# Sheet1.net
KiCad netlist of a schematic drawn in Altium Designer
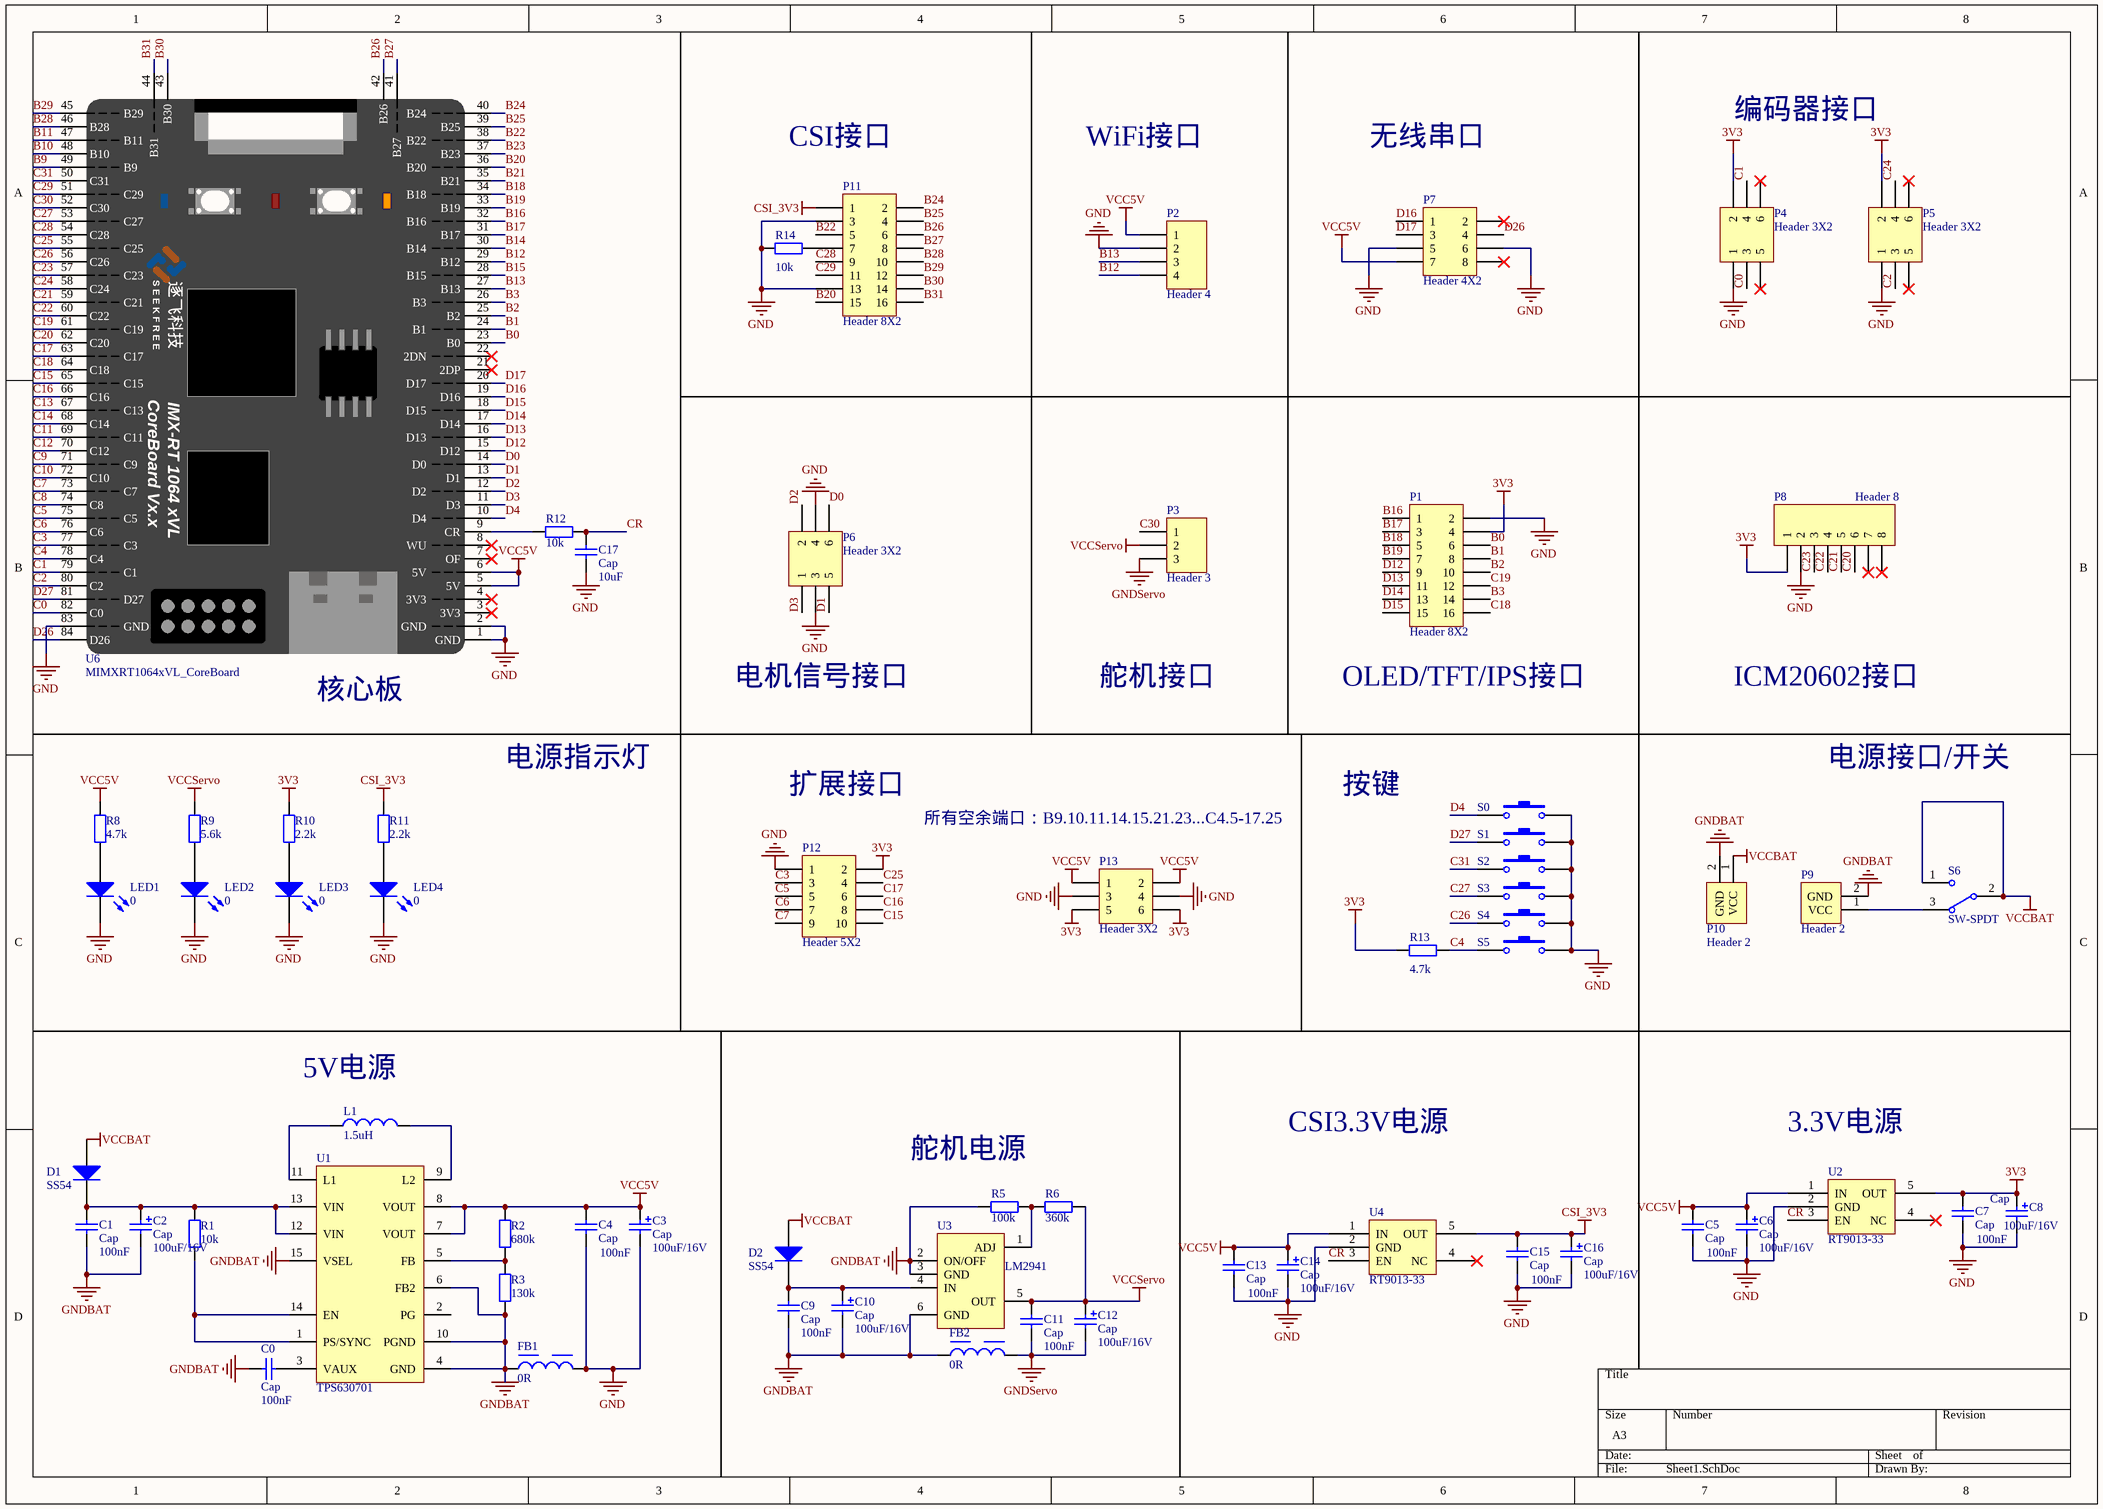
[diagram p0: Sheet1.SchDoc]

(export (version "E")
  (design (tool "Eeschema 10.0.6"))
  (components
    (comp (ref "C0")
      (value "Cap")
      (footprint "0603C")
      (description "Capacitor")
      (fields (field (name "ALTIUM_VALUE") "100nF") (field (name "PUBLISHER") "Altium Limited"))
      (libsource (lib "Schlib1") (part "Cap"))
    )
    (comp (ref "C1")
      (value "Cap")
      (footprint "0603C")
      (description "Capacitor")
      (fields (field (name "ALTIUM_VALUE") "100nF") (field (name "PUBLISHER") "Altium Limited"))
      (libsource (lib "Schlib1") (part "Cap"))
    )
    (comp (ref "C2")
      (value "Cap")
      (footprint "电解电容")
      (description "Capacitor")
      (fields (field (name "ALTIUM_VALUE") "100uF/16V") (field (name "PUBLISHER") "Altium Limited"))
      (libsource (lib "Schlib1") (part "Cap2"))
    )
    (comp (ref "C3")
      (value "Cap")
      (footprint "电解电容")
      (description "Capacitor")
      (fields (field (name "ALTIUM_VALUE") "100uF/16V") (field (name "PUBLISHER") "Altium Limited"))
      (libsource (lib "Schlib1") (part "Cap2"))
    )
    (comp (ref "C4")
      (value "Cap")
      (footprint "0603C")
      (description "Capacitor")
      (fields (field (name "ALTIUM_VALUE") "100nF") (field (name "PUBLISHER") "Altium Limited"))
      (libsource (lib "Schlib1") (part "Cap"))
    )
    (comp (ref "C5")
      (value "Cap")
      (footprint "0603C")
      (description "Capacitor")
      (fields (field (name "ALTIUM_VALUE") "100nF") (field (name "PUBLISHER") "Altium Limited"))
      (libsource (lib "Schlib1") (part "Cap"))
    )
    (comp (ref "C6")
      (value "Cap")
      (footprint "电解电容")
      (description "Capacitor")
      (fields (field (name "ALTIUM_VALUE") "100uF/16V") (field (name "PUBLISHER") "Altium Limited"))
      (libsource (lib "Schlib1") (part "Cap2"))
    )
    (comp (ref "C7")
      (value "Cap")
      (footprint "0603C")
      (description "Capacitor")
      (fields (field (name "ALTIUM_VALUE") "100nF") (field (name "PUBLISHER") "Altium Limited"))
      (libsource (lib "Schlib1") (part "Cap"))
    )
    (comp (ref "C8")
      (value "Cap")
      (footprint "电解电容")
      (description "Capacitor")
      (fields (field (name "ALTIUM_VALUE") "100uF/16V") (field (name "PUBLISHER") "Altium Limited"))
      (libsource (lib "Schlib1") (part "Cap2"))
    )
    (comp (ref "C9")
      (value "Cap")
      (footprint "0603C")
      (description "Capacitor")
      (fields (field (name "ALTIUM_VALUE") "100nF") (field (name "PUBLISHER") "Altium Limited"))
      (libsource (lib "Schlib1") (part "Cap"))
    )
    (comp (ref "C10")
      (value "Cap")
      (footprint "电解电容")
      (description "Capacitor")
      (fields (field (name "ALTIUM_VALUE") "100uF/16V") (field (name "PUBLISHER") "Altium Limited"))
      (libsource (lib "Schlib1") (part "Cap2"))
    )
    (comp (ref "C11")
      (value "Cap")
      (footprint "0603C")
      (description "Capacitor")
      (fields (field (name "ALTIUM_VALUE") "100nF") (field (name "PUBLISHER") "Altium Limited"))
      (libsource (lib "Schlib1") (part "Cap"))
    )
    (comp (ref "C12")
      (value "Cap")
      (footprint "电解电容")
      (description "Capacitor")
      (fields (field (name "ALTIUM_VALUE") "100uF/16V") (field (name "PUBLISHER") "Altium Limited"))
      (libsource (lib "Schlib1") (part "Cap2"))
    )
    (comp (ref "C13")
      (value "Cap")
      (footprint "0603C")
      (description "Capacitor")
      (fields (field (name "ALTIUM_VALUE") "100nF") (field (name "PUBLISHER") "Altium Limited"))
      (libsource (lib "Schlib1") (part "Cap"))
    )
    (comp (ref "C14")
      (value "Cap")
      (footprint "电解电容")
      (description "Capacitor")
      (fields (field (name "ALTIUM_VALUE") "100uF/16V") (field (name "PUBLISHER") "Altium Limited"))
      (libsource (lib "Schlib1") (part "Cap2"))
    )
    (comp (ref "C15")
      (value "Cap")
      (footprint "0603C")
      (description "Capacitor")
      (fields (field (name "ALTIUM_VALUE") "100nF") (field (name "PUBLISHER") "Altium Limited"))
      (libsource (lib "Schlib1") (part "Cap"))
    )
    (comp (ref "C16")
      (value "Cap")
      (footprint "电解电容")
      (description "Capacitor")
      (fields (field (name "ALTIUM_VALUE") "100uF/16V") (field (name "PUBLISHER") "Altium Limited"))
      (libsource (lib "Schlib1") (part "Cap2"))
    )
    (comp (ref "C17")
      (value "Cap")
      (footprint "0603C")
      (description "Capacitor")
      (fields (field (name "ALTIUM_VALUE") "10uF") (field (name "PUBLISHER") "Altium Limited"))
      (libsource (lib "Schlib1") (part "Cap"))
    )
    (comp (ref "D1")
      (value "SS54")
      (footprint "ss54")
      (description "Default Diode")
      (fields (field (name "PUBLISHER") "Altium Limited"))
      (libsource (lib "Schlib1") (part "Diode_1"))
    )
    (comp (ref "D2")
      (value "SS54")
      (footprint "ss54")
      (description "Default Diode")
      (fields (field (name "PUBLISHER") "Altium Limited"))
      (libsource (lib "Schlib1") (part "Diode_1"))
    )
    (comp (ref "FB1")
      (value "0R")
      (footprint "0805")
      (description "Inductor")
      (fields (field (name "PUBLISHER") "Altium Limited"))
      (libsource (lib "Schlib1") (part "FB"))
    )
    (comp (ref "FB2")
      (value "0R")
      (footprint "0805")
      (description "Inductor")
      (fields (field (name "PUBLISHER") "Altium Limited"))
      (libsource (lib "Schlib1") (part "FB"))
    )
    (comp (ref "L1")
      (value "1.5uH")
      (footprint "1R5")
      (description "Inductor")
      (fields (field (name "PUBLISHER") "Altium Limited"))
      (libsource (lib "Schlib1") (part "Inductor_2"))
    )
    (comp (ref "LED1")
      (value "0")
      (footprint "0603C")
      (description "Typical RED, GREEN, YELLOW, AMBER GaAs LED")
      (fields (field (name "PUBLISHER") "Altium Limited"))
      (libsource (lib "Schlib1") (part "LED2"))
    )
    (comp (ref "LED2")
      (value "0")
      (footprint "0603C")
      (description "Typical RED, GREEN, YELLOW, AMBER GaAs LED")
      (fields (field (name "PUBLISHER") "Altium Limited"))
      (libsource (lib "Schlib1") (part "LED2"))
    )
    (comp (ref "LED3")
      (value "0")
      (footprint "0603C")
      (description "Typical RED, GREEN, YELLOW, AMBER GaAs LED")
      (fields (field (name "PUBLISHER") "Altium Limited"))
      (libsource (lib "Schlib1") (part "LED2"))
    )
    (comp (ref "LED4")
      (value "0")
      (footprint "0603C")
      (description "Typical RED, GREEN, YELLOW, AMBER GaAs LED")
      (fields (field (name "PUBLISHER") "Altium Limited"))
      (libsource (lib "Schlib1") (part "LED2"))
    )
    (comp (ref "P1")
      (value "Header 8X2")
      (footprint "HDR2X8")
      (description "Header, 8-Pin, Dual row")
      (fields (field (name "PUBLISHER") "Altium Limited"))
      (libsource (lib "Miscellaneous Connectors") (part "Header 8X2"))
    )
    (comp (ref "P2")
      (value "Header 4")
      (footprint "HDR1X4")
      (description "Header, 4-Pin")
      (fields (field (name "PUBLISHER") "Altium Limited"))
      (libsource (lib "Miscellaneous Connectors") (part "Header 4"))
    )
    (comp (ref "P3")
      (value "Header 3")
      (footprint "HDR1X3")
      (description "Header, 3-Pin")
      (fields (field (name "PUBLISHER") "Altium Limited"))
      (libsource (lib "Miscellaneous Connectors") (part "Header 3"))
    )
    (comp (ref "P4")
      (value "Header 3X2")
      (footprint "HDR2X3")
      (description "Header, 3-Pin, Dual row")
      (fields (field (name "PUBLISHER") "Altium Limited"))
      (libsource (lib "Miscellaneous Connectors") (part "Header 3X2"))
    )
    (comp (ref "P5")
      (value "Header 3X2")
      (footprint "HDR2X3")
      (description "Header, 3-Pin, Dual row")
      (fields (field (name "PUBLISHER") "Altium Limited"))
      (libsource (lib "Miscellaneous Connectors") (part "Header 3X2"))
    )
    (comp (ref "P6")
      (value "Header 3X2")
      (footprint "HDR2X3")
      (description "Header, 3-Pin, Dual row")
      (fields (field (name "PUBLISHER") "Altium Limited"))
      (libsource (lib "Miscellaneous Connectors") (part "Header 3X2"))
    )
    (comp (ref "P7")
      (value "Header 4X2")
      (footprint "HDR2X4")
      (description "Header, 4-Pin, Dual row")
      (fields (field (name "PUBLISHER") "Altium Limited"))
      (libsource (lib "Miscellaneous Connectors") (part "Header 4X2"))
    )
    (comp (ref "P8")
      (value "Header 8")
      (footprint "HDR1X8")
      (description "Header, 8-Pin")
      (fields (field (name "PUBLISHER") "Altium Limited"))
      (libsource (lib "Miscellaneous Connectors") (part "Header 8"))
    )
    (comp (ref "P9")
      (value "Header 2")
      (footprint "VCCBAT")
      (description "Header, 2-Pin")
      (fields (field (name "PUBLISHER") "Altium Limited"))
      (libsource (lib "Schlib1") (part "Header 2_1"))
    )
    (comp (ref "P10")
      (value "Header 2")
      (footprint "VCCBAT")
      (description "Header, 2-Pin")
      (fields (field (name "PUBLISHER") "Altium Limited"))
      (libsource (lib "Schlib1") (part "Header 2_2"))
    )
    (comp (ref "P11")
      (value "Header 8X2")
      (footprint "HDR2X8")
      (description "Header, 8-Pin, Dual row")
      (fields (field (name "PUBLISHER") "Altium Limited"))
      (libsource (lib "Miscellaneous Connectors") (part "Header 8X2"))
    )
    (comp (ref "P12")
      (value "Header 5X2")
      (footprint "HDR2X5")
      (description "Header, 5-Pin, Dual row")
      (fields (field (name "PUBLISHER") "Altium Limited"))
      (libsource (lib "Miscellaneous Connectors") (part "Header 5X2"))
    )
    (comp (ref "P13")
      (value "Header 3X2")
      (footprint "HDR2X3")
      (description "Header, 3-Pin, Dual row")
      (fields (field (name "PUBLISHER") "Altium Limited"))
      (libsource (lib "") (part "Header 3X2_1"))
    )
    (comp (ref "R1")
      (value "10k")
      (footprint "0603R")
      (description "Resistor")
      (fields (field (name "Comment") "Res2") (field (name "PUBLISHER") "Altium Limited"))
      (libsource (lib "Schlib1") (part "Res2"))
    )
    (comp (ref "R2")
      (value "680k")
      (footprint "0603R")
      (description "Resistor")
      (fields (field (name "Comment") "Res2") (field (name "PUBLISHER") "Altium Limited"))
      (libsource (lib "Schlib1") (part "Res2"))
    )
    (comp (ref "R3")
      (value "130k")
      (footprint "0603R")
      (description "Resistor 改成了120k")
      (fields (field (name "Comment") "Res2") (field (name "PUBLISHER") "Altium Limited"))
      (libsource (lib "Schlib1") (part "Res2"))
    )
    (comp (ref "R5")
      (value "100k")
      (footprint "0603R")
      (description "Resistor")
      (fields (field (name "Comment") "Res2") (field (name "PUBLISHER") "Altium Limited"))
      (libsource (lib "") (part "Res2_1"))
    )
    (comp (ref "R6")
      (value "360k")
      (footprint "0603R")
      (description "Resistor 改成了330k")
      (fields (field (name "Comment") "Res2") (field (name "PUBLISHER") "Altium Limited"))
      (libsource (lib "") (part "Res2_1"))
    )
    (comp (ref "R8")
      (value "4.7k")
      (footprint "0603R")
      (description "Resistor")
      (fields (field (name "Comment") "Res2") (field (name "PUBLISHER") "Altium Limited"))
      (libsource (lib "Schlib1") (part "Res2"))
    )
    (comp (ref "R9")
      (value "5.6k")
      (footprint "0603R")
      (description "Resistor改成了5.1k")
      (fields (field (name "Comment") "Res2") (field (name "PUBLISHER") "Altium Limited"))
      (libsource (lib "Schlib1") (part "Res2"))
    )
    (comp (ref "R10")
      (value "2.2k")
      (footprint "0603R")
      (description "Resistor")
      (fields (field (name "Comment") "Res2") (field (name "PUBLISHER") "Altium Limited"))
      (libsource (lib "Schlib1") (part "Res2"))
    )
    (comp (ref "R11")
      (value "2.2k")
      (footprint "0603R")
      (description "Resistor")
      (fields (field (name "Comment") "Res2") (field (name "PUBLISHER") "Altium Limited"))
      (libsource (lib "Schlib1") (part "Res2"))
    )
    (comp (ref "R12")
      (value "10k")
      (footprint "0603R")
      (description "Resistor")
      (fields (field (name "Comment") "Res2") (field (name "PUBLISHER") "Altium Limited"))
      (libsource (lib "") (part "Res2_1"))
    )
    (comp (ref "R13")
      (value "4.7k")
      (footprint "0603R")
      (description "Resistor")
      (fields (field (name "Comment") "Res2") (field (name "PUBLISHER") "Altium Limited"))
      (libsource (lib "") (part "Res2_1"))
    )
    (comp (ref "R14")
      (value "10k")
      (footprint "0603R")
      (description "Resistor")
      (fields (field (name "Comment") "Res2") (field (name "PUBLISHER") "Altium Limited"))
      (libsource (lib "") (part "Res2_1"))
    )
    (comp (ref "S0")
      (value "~")
      (footprint "SPST-2")
      (description "Switch")
      (fields (field (name "PUBLISHER") "Altium Limited"))
      (libsource (lib "Miscellaneous Devices") (part "SW-PB"))
    )
    (comp (ref "S1")
      (value "~")
      (footprint "SPST-2")
      (description "Switch")
      (fields (field (name "PUBLISHER") "Altium Limited"))
      (libsource (lib "Miscellaneous Devices") (part "SW-PB"))
    )
    (comp (ref "S2")
      (value "~")
      (footprint "SPST-2")
      (description "Switch")
      (fields (field (name "PUBLISHER") "Altium Limited"))
      (libsource (lib "Miscellaneous Devices") (part "SW-PB"))
    )
    (comp (ref "S3")
      (value "~")
      (footprint "SPST-2")
      (description "Switch")
      (fields (field (name "PUBLISHER") "Altium Limited"))
      (libsource (lib "Miscellaneous Devices") (part "SW-PB"))
    )
    (comp (ref "S4")
      (value "~")
      (footprint "SPST-2")
      (description "Switch")
      (fields (field (name "PUBLISHER") "Altium Limited"))
      (libsource (lib "Miscellaneous Devices") (part "SW-PB"))
    )
    (comp (ref "S5")
      (value "~")
      (footprint "SPST-2")
      (description "Switch")
      (fields (field (name "PUBLISHER") "Altium Limited"))
      (libsource (lib "Miscellaneous Devices") (part "SW-PB"))
    )
    (comp (ref "S6")
      (value "SW-SPDT")
      (footprint "SW")
      (description "SPDT Subminiature Toggle Switch, Right Angle Mounting, Vertical Actuation")
      (fields (field (name "PUBLISHER") "Altium Limited"))
      (libsource (lib "Miscellaneous Devices") (part "SW-SPDT"))
    )
    (comp (ref "U1") (value "TPS630701") (footprint "63070") (libsource (lib "Schlib1") (part "TPS630701")))
    (comp (ref "U2")
      (value "RT9013-33")
      (footprint "SOT23-5_L")
      (libsource (lib "Schlib1") (part "RT9013-33"))
    )
    (comp (ref "U3")
      (value "LM2941")
      (footprint "TO-263-5L")
      (description "Header, 4-Pin")
      (fields (field (name "PUBLISHER") "Altium Limited"))
      (libsource (lib "Schlib1") (part "LM2941"))
    )
    (comp (ref "U4")
      (value "RT9013-33")
      (footprint "SOT23-5_L")
      (libsource (lib "Schlib1") (part "RT9013-33"))
    )
    (comp (ref "U6")
      (value "MIMXRT1064xVL_CoreBoard")
      (footprint "MIMXRT1064xVL_CoreBoard")
      (description "逐飞科技i.MX RT1064核心板整体原理，可直接使用")
      (libsource (lib "RT1064 V1.2核心板原理库") (part "MIMXRT1064xVL_CoreBoard"))
    )
  )
  (nets
    (net (code "1") (name "/B0") (class "Default")
      (node (ref "P1") (pin "6") (pinfunction "6_6") (pintype "passive"))
      (node (ref "U6") (pin "23") (pinfunction "B0_23") (pintype "passive"))
    )
    (net (code "2") (name "/B1") (class "Default")
      (node (ref "P1") (pin "8") (pinfunction "8_8") (pintype "passive"))
      (node (ref "U6") (pin "24") (pinfunction "B1_24") (pintype "passive"))
    )
    (net (code "3") (name "/B2") (class "Default")
      (node (ref "P1") (pin "10") (pinfunction "10_10") (pintype "passive"))
      (node (ref "U6") (pin "25") (pinfunction "B2_25") (pintype "passive"))
    )
    (net (code "4") (name "/B3") (class "Default")
      (node (ref "P1") (pin "14") (pinfunction "14_14") (pintype "passive"))
      (node (ref "U6") (pin "26") (pinfunction "B3_26") (pintype "passive"))
    )
    (net (code "5") (name "/B9") (class "Default")
      (node (ref "U6") (pin "49") (pinfunction "B9_49") (pintype "passive"))
    )
    (net (code "6") (name "/B10") (class "Default")
      (node (ref "U6") (pin "48") (pinfunction "B10_48") (pintype "passive"))
    )
    (net (code "7") (name "/B11") (class "Default")
      (node (ref "U6") (pin "47") (pinfunction "B11_47") (pintype "passive"))
    )
    (net (code "8") (name "/B12") (class "Default")
      (node (ref "P2") (pin "4") (pinfunction "4_4") (pintype "passive"))
      (node (ref "U6") (pin "29") (pinfunction "B12_29") (pintype "passive"))
    )
    (net (code "9") (name "/B13") (class "Default")
      (node (ref "P2") (pin "3") (pinfunction "3_3") (pintype "passive"))
      (node (ref "U6") (pin "27") (pinfunction "B13_27") (pintype "passive"))
    )
    (net (code "10") (name "/B14") (class "Default")
      (node (ref "U6") (pin "30") (pinfunction "B14_30") (pintype "passive"))
    )
    (net (code "11") (name "/B15") (class "Default")
      (node (ref "U6") (pin "28") (pinfunction "B15_28") (pintype "passive"))
    )
    (net (code "12") (name "/B16") (class "Default")
      (node (ref "P1") (pin "1") (pinfunction "1_1") (pintype "passive"))
      (node (ref "U6") (pin "32") (pinfunction "B16_32") (pintype "passive"))
    )
    (net (code "13") (name "/B17") (class "Default")
      (node (ref "P1") (pin "3") (pinfunction "3_3") (pintype "passive"))
      (node (ref "U6") (pin "31") (pinfunction "B17_31") (pintype "passive"))
    )
    (net (code "14") (name "/B18") (class "Default")
      (node (ref "P1") (pin "5") (pinfunction "5_5") (pintype "passive"))
      (node (ref "U6") (pin "34") (pinfunction "B18_34") (pintype "passive"))
    )
    (net (code "15") (name "/B19") (class "Default")
      (node (ref "P1") (pin "7") (pinfunction "7_7") (pintype "passive"))
      (node (ref "U6") (pin "33") (pinfunction "B19_33") (pintype "passive"))
    )
    (net (code "16") (name "/B20") (class "Default")
      (node (ref "P11") (pin "15") (pinfunction "15_15") (pintype "passive"))
      (node (ref "U6") (pin "36") (pinfunction "B20_36") (pintype "passive"))
    )
    (net (code "17") (name "/B21") (class "Default")
      (node (ref "U6") (pin "35") (pinfunction "B21_35") (pintype "passive"))
    )
    (net (code "18") (name "/B22") (class "Default")
      (node (ref "P11") (pin "5") (pinfunction "5_5") (pintype "passive"))
      (node (ref "U6") (pin "38") (pinfunction "B22_38") (pintype "passive"))
    )
    (net (code "19") (name "/B23") (class "Default")
      (node (ref "U6") (pin "37") (pinfunction "B23_37") (pintype "passive"))
    )
    (net (code "20") (name "/B24") (class "Default")
      (node (ref "P11") (pin "2") (pinfunction "2_2") (pintype "passive"))
      (node (ref "U6") (pin "40") (pinfunction "B24_40") (pintype "passive"))
    )
    (net (code "21") (name "/B25") (class "Default")
      (node (ref "P11") (pin "4") (pinfunction "4_4") (pintype "passive"))
      (node (ref "U6") (pin "39") (pinfunction "B25_39") (pintype "passive"))
    )
    (net (code "22") (name "/B26") (class "Default")
      (node (ref "P11") (pin "6") (pinfunction "6_6") (pintype "passive"))
      (node (ref "U6") (pin "42") (pinfunction "B26_42") (pintype "passive"))
    )
    (net (code "23") (name "/B27") (class "Default")
      (node (ref "P11") (pin "8") (pinfunction "8_8") (pintype "passive"))
      (node (ref "U6") (pin "41") (pinfunction "B27_41") (pintype "passive"))
    )
    (net (code "24") (name "/B28") (class "Default")
      (node (ref "P11") (pin "10") (pinfunction "10_10") (pintype "passive"))
      (node (ref "U6") (pin "46") (pinfunction "B28_46") (pintype "passive"))
    )
    (net (code "25") (name "/B29") (class "Default")
      (node (ref "P11") (pin "12") (pinfunction "12_12") (pintype "passive"))
      (node (ref "U6") (pin "45") (pinfunction "B29_45") (pintype "passive"))
    )
    (net (code "26") (name "/B30") (class "Default")
      (node (ref "P11") (pin "14") (pinfunction "14_14") (pintype "passive"))
      (node (ref "U6") (pin "43") (pinfunction "B30_43") (pintype "passive"))
    )
    (net (code "27") (name "/B31") (class "Default")
      (node (ref "P11") (pin "16") (pinfunction "16_16") (pintype "passive"))
      (node (ref "U6") (pin "44") (pinfunction "B31_44") (pintype "passive"))
    )
    (net (code "28") (name "/C0") (class "Default")
      (node (ref "P4") (pin "3") (pinfunction "3_3") (pintype "passive"))
      (node (ref "U6") (pin "82") (pinfunction "C0_82") (pintype "passive"))
    )
    (net (code "29") (name "/C1") (class "Default")
      (node (ref "P4") (pin "4") (pinfunction "4_4") (pintype "passive"))
      (node (ref "U6") (pin "79") (pinfunction "C1_79") (pintype "passive"))
    )
    (net (code "30") (name "/C2") (class "Default")
      (node (ref "P5") (pin "3") (pinfunction "3_3") (pintype "passive"))
      (node (ref "U6") (pin "80") (pinfunction "C2_80") (pintype "passive"))
    )
    (net (code "31") (name "/C3") (class "Default")
      (node (ref "P12") (pin "3") (pinfunction "3_3") (pintype "passive"))
      (node (ref "U6") (pin "77") (pinfunction "C3_77") (pintype "passive"))
    )
    (net (code "32") (name "/C4") (class "Default")
      (node (ref "R13") (pin "2") (pinfunction "2_2") (pintype "passive"))
      (node (ref "S5") (pin "1") (pinfunction "1_1") (pintype "passive"))
      (node (ref "U6") (pin "78") (pinfunction "C4_78") (pintype "passive"))
    )
    (net (code "33") (name "/C5") (class "Default")
      (node (ref "P12") (pin "5") (pinfunction "5_5") (pintype "passive"))
      (node (ref "U6") (pin "75") (pinfunction "C5_75") (pintype "passive"))
    )
    (net (code "34") (name "/C6") (class "Default")
      (node (ref "P12") (pin "7") (pinfunction "7_7") (pintype "passive"))
      (node (ref "U6") (pin "76") (pinfunction "C6_76") (pintype "passive"))
    )
    (net (code "35") (name "/C7") (class "Default")
      (node (ref "P12") (pin "9") (pinfunction "9_9") (pintype "passive"))
      (node (ref "U6") (pin "73") (pinfunction "C7_73") (pintype "passive"))
    )
    (net (code "36") (name "/C8") (class "Default")
      (node (ref "U6") (pin "74") (pinfunction "C8_74") (pintype "passive"))
    )
    (net (code "37") (name "/C9") (class "Default")
      (node (ref "U6") (pin "71") (pinfunction "C9_71") (pintype "passive"))
    )
    (net (code "38") (name "/C10") (class "Default")
      (node (ref "U6") (pin "72") (pinfunction "C10_72") (pintype "passive"))
    )
    (net (code "39") (name "/C11") (class "Default")
      (node (ref "U6") (pin "69") (pinfunction "C11_69") (pintype "passive"))
    )
    (net (code "40") (name "/C12") (class "Default")
      (node (ref "U6") (pin "70") (pinfunction "C12_70") (pintype "passive"))
    )
    (net (code "41") (name "/C13") (class "Default")
      (node (ref "U6") (pin "67") (pinfunction "C13_67") (pintype "passive"))
    )
    (net (code "42") (name "/C14") (class "Default")
      (node (ref "U6") (pin "68") (pinfunction "C14_68") (pintype "passive"))
    )
    (net (code "43") (name "/C15") (class "Default")
      (node (ref "P12") (pin "10") (pinfunction "10_10") (pintype "passive"))
      (node (ref "U6") (pin "65") (pinfunction "C15_65") (pintype "passive"))
    )
    (net (code "44") (name "/C16") (class "Default")
      (node (ref "P12") (pin "8") (pinfunction "8_8") (pintype "passive"))
      (node (ref "U6") (pin "66") (pinfunction "C16_66") (pintype "passive"))
    )
    (net (code "45") (name "/C17") (class "Default")
      (node (ref "P12") (pin "6") (pinfunction "6_6") (pintype "passive"))
      (node (ref "U6") (pin "63") (pinfunction "C17_63") (pintype "passive"))
    )
    (net (code "46") (name "/C18") (class "Default")
      (node (ref "P1") (pin "16") (pinfunction "16_16") (pintype "passive"))
      (node (ref "U6") (pin "64") (pinfunction "C18_64") (pintype "passive"))
    )
    (net (code "47") (name "/C19") (class "Default")
      (node (ref "P1") (pin "12") (pinfunction "12_12") (pintype "passive"))
      (node (ref "U6") (pin "61") (pinfunction "C19_61") (pintype "passive"))
    )
    (net (code "48") (name "/C20") (class "Default")
      (node (ref "P8") (pin "6") (pinfunction "6_6") (pintype "passive"))
      (node (ref "U6") (pin "62") (pinfunction "C20_62") (pintype "passive"))
    )
    (net (code "49") (name "/C21") (class "Default")
      (node (ref "P8") (pin "5") (pinfunction "5_5") (pintype "passive"))
      (node (ref "U6") (pin "59") (pinfunction "C21_59") (pintype "passive"))
    )
    (net (code "50") (name "/C22") (class "Default")
      (node (ref "P8") (pin "4") (pinfunction "4_4") (pintype "passive"))
      (node (ref "U6") (pin "60") (pinfunction "C22_60") (pintype "passive"))
    )
    (net (code "51") (name "/C23") (class "Default")
      (node (ref "P8") (pin "3") (pinfunction "3_3") (pintype "passive"))
      (node (ref "U6") (pin "57") (pinfunction "C23_57") (pintype "passive"))
    )
    (net (code "52") (name "/C24") (class "Default")
      (node (ref "P5") (pin "4") (pinfunction "4_4") (pintype "passive"))
      (node (ref "U6") (pin "58") (pinfunction "C24_58") (pintype "passive"))
    )
    (net (code "53") (name "/C25") (class "Default")
      (node (ref "P12") (pin "4") (pinfunction "4_4") (pintype "passive"))
      (node (ref "U6") (pin "55") (pinfunction "C25_55") (pintype "passive"))
    )
    (net (code "54") (name "/C26") (class "Default")
      (node (ref "S4") (pin "1") (pinfunction "1_1") (pintype "passive"))
      (node (ref "U6") (pin "56") (pinfunction "C26_56") (pintype "passive"))
    )
    (net (code "55") (name "/C27") (class "Default")
      (node (ref "S3") (pin "1") (pinfunction "1_1") (pintype "passive"))
      (node (ref "U6") (pin "53") (pinfunction "C27_53") (pintype "passive"))
    )
    (net (code "56") (name "/C28") (class "Default")
      (node (ref "P11") (pin "9") (pinfunction "9_9") (pintype "passive"))
      (node (ref "U6") (pin "54") (pinfunction "C28_54") (pintype "passive"))
    )
    (net (code "57") (name "/C29") (class "Default")
      (node (ref "P11") (pin "11") (pinfunction "11_11") (pintype "passive"))
      (node (ref "U6") (pin "51") (pinfunction "C29_51") (pintype "passive"))
    )
    (net (code "58") (name "/C30") (class "Default")
      (node (ref "P3") (pin "1") (pinfunction "1_1") (pintype "passive"))
      (node (ref "U6") (pin "52") (pinfunction "C30_52") (pintype "passive"))
    )
    (net (code "59") (name "/C31") (class "Default")
      (node (ref "S2") (pin "1") (pinfunction "1_1") (pintype "passive"))
      (node (ref "U6") (pin "50") (pinfunction "C31_50") (pintype "passive"))
    )
    (net (code "60") (name "/CR") (class "Default")
      (node (ref "C17") (pin "2") (pinfunction "2_2") (pintype "passive"))
      (node (ref "R12") (pin "2") (pinfunction "2_2") (pintype "passive"))
      (node (ref "U2") (pin "3") (pinfunction "EN_3") (pintype "passive"))
      (node (ref "U4") (pin "3") (pinfunction "EN_3") (pintype "passive"))
    )
    (net (code "61") (name "/D0") (class "Default")
      (node (ref "P6") (pin "6") (pinfunction "6_6") (pintype "passive"))
      (node (ref "U6") (pin "14") (pinfunction "D0_14") (pintype "passive"))
    )
    (net (code "62") (name "/D1") (class "Default")
      (node (ref "P6") (pin "5") (pinfunction "5_5") (pintype "passive"))
      (node (ref "U6") (pin "13") (pinfunction "D1_13") (pintype "passive"))
    )
    (net (code "63") (name "/D2") (class "Default")
      (node (ref "P6") (pin "2") (pinfunction "2_2") (pintype "passive"))
      (node (ref "U6") (pin "12") (pinfunction "D2_12") (pintype "passive"))
    )
    (net (code "64") (name "/D3") (class "Default")
      (node (ref "P6") (pin "1") (pinfunction "1_1") (pintype "passive"))
      (node (ref "U6") (pin "11") (pinfunction "D3_11") (pintype "passive"))
    )
    (net (code "65") (name "/D4") (class "Default")
      (node (ref "S0") (pin "1") (pinfunction "1_1") (pintype "passive"))
      (node (ref "U6") (pin "10") (pinfunction "D4_10") (pintype "passive"))
    )
    (net (code "66") (name "/D12") (class "Default")
      (node (ref "P1") (pin "9") (pinfunction "9_9") (pintype "passive"))
      (node (ref "U6") (pin "15") (pinfunction "D12_15") (pintype "passive"))
    )
    (net (code "67") (name "/D13") (class "Default")
      (node (ref "P1") (pin "11") (pinfunction "11_11") (pintype "passive"))
      (node (ref "U6") (pin "16") (pinfunction "D13_16") (pintype "passive"))
    )
    (net (code "68") (name "/D14") (class "Default")
      (node (ref "P1") (pin "13") (pinfunction "13_13") (pintype "passive"))
      (node (ref "U6") (pin "17") (pinfunction "D14_17") (pintype "passive"))
    )
    (net (code "69") (name "/D15") (class "Default")
      (node (ref "P1") (pin "15") (pinfunction "15_15") (pintype "passive"))
      (node (ref "U6") (pin "18") (pinfunction "D15_18") (pintype "passive"))
    )
    (net (code "70") (name "/D16") (class "Default")
      (node (ref "P7") (pin "1") (pinfunction "1_1") (pintype "passive"))
      (node (ref "U6") (pin "19") (pinfunction "D16_19") (pintype "passive"))
    )
    (net (code "71") (name "/D17") (class "Default")
      (node (ref "P7") (pin "3") (pinfunction "3_3") (pintype "passive"))
      (node (ref "U6") (pin "20") (pinfunction "D17_20") (pintype "passive"))
    )
    (net (code "72") (name "/D26") (class "Default")
      (node (ref "P7") (pin "4") (pinfunction "4_4") (pintype "passive"))
      (node (ref "U6") (pin "84") (pinfunction "D26_84") (pintype "passive"))
    )
    (net (code "73") (name "/D27") (class "Default")
      (node (ref "S1") (pin "1") (pinfunction "1_1") (pintype "passive"))
      (node (ref "U6") (pin "81") (pinfunction "D27_81") (pintype "passive"))
    )
    (net (code "74") (name "3V3") (class "Default")
      (node (ref "C7") (pin "2") (pinfunction "2_2") (pintype "passive"))
      (node (ref "C8") (pin "1") (pinfunction "1_1") (pintype "passive"))
      (node (ref "P1") (pin "4") (pinfunction "4_4") (pintype "passive"))
      (node (ref "P12") (pin "2") (pinfunction "2_2") (pintype "passive"))
      (node (ref "P13") (pin "5") (pinfunction "5_5") (pintype "passive"))
      (node (ref "P13") (pin "6") (pinfunction "6_6") (pintype "passive"))
      (node (ref "P4") (pin "2") (pinfunction "2_2") (pintype "passive"))
      (node (ref "P5") (pin "2") (pinfunction "2_2") (pintype "passive"))
      (node (ref "P8") (pin "1") (pinfunction "1_1") (pintype "passive"))
      (node (ref "R10") (pin "2") (pinfunction "2_2") (pintype "passive"))
      (node (ref "R13") (pin "1") (pinfunction "1_1") (pintype "passive"))
      (node (ref "U2") (pin "5") (pinfunction "OUT_5") (pintype "passive"))
    )
    (net (code "75") (name "CSI_3V3") (class "Default")
      (node (ref "C15") (pin "2") (pinfunction "2_2") (pintype "passive"))
      (node (ref "C16") (pin "1") (pinfunction "1_1") (pintype "passive"))
      (node (ref "P11") (pin "1") (pinfunction "1_1") (pintype "passive"))
      (node (ref "R11") (pin "2") (pinfunction "2_2") (pintype "passive"))
      (node (ref "U4") (pin "5") (pinfunction "OUT_5") (pintype "passive"))
    )
    (net (code "76") (name "GND") (class "Default")
      (node (ref "C13") (pin "1") (pinfunction "1_1") (pintype "passive"))
      (node (ref "C14") (pin "2") (pinfunction "2_2") (pintype "passive"))
      (node (ref "C15") (pin "1") (pinfunction "1_1") (pintype "passive"))
      (node (ref "C16") (pin "2") (pinfunction "2_2") (pintype "passive"))
      (node (ref "C17") (pin "1") (pinfunction "1_1") (pintype "passive"))
      (node (ref "C3") (pin "2") (pinfunction "2_2") (pintype "passive"))
      (node (ref "C4") (pin "1") (pinfunction "1_1") (pintype "passive"))
      (node (ref "C5") (pin "1") (pinfunction "1_1") (pintype "passive"))
      (node (ref "C6") (pin "2") (pinfunction "2_2") (pintype "passive"))
      (node (ref "C7") (pin "1") (pinfunction "1_1") (pintype "passive"))
      (node (ref "C8") (pin "2") (pinfunction "2_2") (pintype "passive"))
      (node (ref "FB1") (pin "2") (pinfunction "2_2") (pintype "passive"))
      (node (ref "LED1") (pin "2") (pinfunction "K_2") (pintype "passive"))
      (node (ref "LED2") (pin "2") (pinfunction "K_2") (pintype "passive"))
      (node (ref "LED3") (pin "2") (pinfunction "K_2") (pintype "passive"))
      (node (ref "LED4") (pin "2") (pinfunction "K_2") (pintype "passive"))
      (node (ref "P1") (pin "2") (pinfunction "2_2") (pintype "passive"))
      (node (ref "P11") (pin "13") (pinfunction "13_13") (pintype "passive"))
      (node (ref "P11") (pin "3") (pinfunction "3_3") (pintype "passive"))
      (node (ref "P12") (pin "1") (pinfunction "1_1") (pintype "passive"))
      (node (ref "P13") (pin "3") (pinfunction "3_3") (pintype "passive"))
      (node (ref "P13") (pin "4") (pinfunction "4_4") (pintype "passive"))
      (node (ref "P2") (pin "2") (pinfunction "2_2") (pintype "passive"))
      (node (ref "P4") (pin "1") (pinfunction "1_1") (pintype "passive"))
      (node (ref "P5") (pin "1") (pinfunction "1_1") (pintype "passive"))
      (node (ref "P6") (pin "3") (pinfunction "3_3") (pintype "passive"))
      (node (ref "P6") (pin "4") (pinfunction "4_4") (pintype "passive"))
      (node (ref "P7") (pin "5") (pinfunction "5_5") (pintype "passive"))
      (node (ref "P7") (pin "6") (pinfunction "6_6") (pintype "passive"))
      (node (ref "P8") (pin "2") (pinfunction "2_2") (pintype "passive"))
      (node (ref "R14") (pin "1") (pinfunction "1_1") (pintype "passive"))
      (node (ref "S0") (pin "2") (pinfunction "2_2") (pintype "passive"))
      (node (ref "S1") (pin "2") (pinfunction "2_2") (pintype "passive"))
      (node (ref "S2") (pin "2") (pinfunction "2_2") (pintype "passive"))
      (node (ref "S3") (pin "2") (pinfunction "2_2") (pintype "passive"))
      (node (ref "S4") (pin "2") (pinfunction "2_2") (pintype "passive"))
      (node (ref "S5") (pin "2") (pinfunction "2_2") (pintype "passive"))
      (node (ref "U2") (pin "2") (pinfunction "GND_2") (pintype "passive"))
      (node (ref "U4") (pin "2") (pinfunction "GND_2") (pintype "passive"))
      (node (ref "U6") (pin "1") (pinfunction "GND_1") (pintype "passive"))
      (node (ref "U6") (pin "2") (pinfunction "GND_2") (pintype "passive"))
      (node (ref "U6") (pin "83") (pinfunction "GND_83") (pintype "passive"))
    )
    (net (code "77") (name "GNDBAT") (class "Default")
      (node (ref "C0") (pin "2") (pinfunction "2_2") (pintype "passive"))
      (node (ref "C1") (pin "1") (pinfunction "1_1") (pintype "passive"))
      (node (ref "C10") (pin "2") (pinfunction "2_2") (pintype "passive"))
      (node (ref "C2") (pin "2") (pinfunction "2_2") (pintype "passive"))
      (node (ref "C9") (pin "1") (pinfunction "1_1") (pintype "passive"))
      (node (ref "FB1") (pin "1") (pinfunction "1_1") (pintype "passive"))
      (node (ref "FB2") (pin "1") (pinfunction "1_1") (pintype "passive"))
      (node (ref "P10") (pin "2") (pinfunction "GND_2") (pintype "passive"))
      (node (ref "P9") (pin "2") (pinfunction "GND_2") (pintype "passive"))
      (node (ref "R3") (pin "1") (pinfunction "1_1") (pintype "passive"))
      (node (ref "R5") (pin "1") (pinfunction "1_1") (pintype "passive"))
      (node (ref "U1") (pin "10") (pinfunction "PGND_10") (pintype "passive"))
      (node (ref "U1") (pin "15") (pinfunction "VSEL_15") (pintype "passive"))
      (node (ref "U1") (pin "4") (pinfunction "GND_4") (pintype "passive"))
      (node (ref "U1") (pin "6") (pinfunction "FB2_6") (pintype "passive"))
      (node (ref "U3") (pin "2") (pinfunction "ON/OFF_2") (pintype "passive"))
      (node (ref "U3") (pin "3") (pinfunction "GND_3") (pintype "passive"))
      (node (ref "U3") (pin "6") (pinfunction "GND_6") (pintype "passive"))
    )
    (net (code "78") (name "GNDServo") (class "Default")
      (node (ref "C11") (pin "1") (pinfunction "1_1") (pintype "passive"))
      (node (ref "C12") (pin "2") (pinfunction "2_2") (pintype "passive"))
      (node (ref "FB2") (pin "2") (pinfunction "2_2") (pintype "passive"))
      (node (ref "P3") (pin "3") (pinfunction "3_3") (pintype "passive"))
    )
    (net (code "79") (name "Net-(D1-K)") (class "Default")
      (node (ref "C1") (pin "2") (pinfunction "2_2") (pintype "passive"))
      (node (ref "C2") (pin "1") (pinfunction "1_1") (pintype "passive"))
      (node (ref "D1") (pin "2") (pinfunction "K_2") (pintype "passive"))
      (node (ref "R1") (pin "2") (pinfunction "2_2") (pintype "passive"))
      (node (ref "U1") (pin "12") (pinfunction "VIN_12") (pintype "passive"))
      (node (ref "U1") (pin "13") (pinfunction "VIN_13") (pintype "passive"))
    )
    (net (code "80") (name "Net-(D2-K)") (class "Default")
      (node (ref "C10") (pin "1") (pinfunction "1_1") (pintype "passive"))
      (node (ref "C9") (pin "2") (pinfunction "2_2") (pintype "passive"))
      (node (ref "D2") (pin "2") (pinfunction "K_2") (pintype "passive"))
      (node (ref "U3") (pin "4") (pinfunction "IN_4") (pintype "passive"))
    )
    (net (code "81") (name "Net-(LED1-A)") (class "Default")
      (node (ref "LED1") (pin "1") (pinfunction "A_1") (pintype "passive"))
      (node (ref "R8") (pin "1") (pinfunction "1_1") (pintype "passive"))
    )
    (net (code "82") (name "Net-(LED2-A)") (class "Default")
      (node (ref "LED2") (pin "1") (pinfunction "A_1") (pintype "passive"))
      (node (ref "R9") (pin "1") (pinfunction "1_1") (pintype "passive"))
    )
    (net (code "83") (name "Net-(LED3-A)") (class "Default")
      (node (ref "LED3") (pin "1") (pinfunction "A_1") (pintype "passive"))
      (node (ref "R10") (pin "1") (pinfunction "1_1") (pintype "passive"))
    )
    (net (code "84") (name "Net-(LED4-A)") (class "Default")
      (node (ref "LED4") (pin "1") (pinfunction "A_1") (pintype "passive"))
      (node (ref "R11") (pin "1") (pinfunction "1_1") (pintype "passive"))
    )
    (net (code "85") (name "Net-(P9-VCC)") (class "Default")
      (node (ref "P9") (pin "1") (pinfunction "VCC_1") (pintype "passive"))
      (node (ref "S6") (pin "3") (pinfunction "3_3") (pintype "passive"))
    )
    (net (code "86") (name "Net-(P11-Pad7)") (class "Default")
      (node (ref "P11") (pin "7") (pinfunction "7_7") (pintype "passive"))
      (node (ref "R14") (pin "2") (pinfunction "2_2") (pintype "passive"))
    )
    (net (code "87") (name "Net-(U1-EN)") (class "Default")
      (node (ref "R1") (pin "1") (pinfunction "1_1") (pintype "passive"))
      (node (ref "U1") (pin "1") (pinfunction "PS/SYNC_1") (pintype "passive"))
      (node (ref "U1") (pin "14") (pinfunction "EN_14") (pintype "passive"))
    )
    (net (code "88") (name "Net-(U1-FB)") (class "Default")
      (node (ref "R2") (pin "1") (pinfunction "1_1") (pintype "passive"))
      (node (ref "R3") (pin "2") (pinfunction "2_2") (pintype "passive"))
      (node (ref "U1") (pin "5") (pinfunction "FB_5") (pintype "passive"))
    )
    (net (code "89") (name "Net-(U1-L1)") (class "Default")
      (node (ref "L1") (pin "1") (pinfunction "1_1") (pintype "passive"))
      (node (ref "U1") (pin "11") (pinfunction "L1_11") (pintype "passive"))
    )
    (net (code "90") (name "Net-(U1-L2)") (class "Default")
      (node (ref "L1") (pin "2") (pinfunction "2_2") (pintype "passive"))
      (node (ref "U1") (pin "9") (pinfunction "L2_9") (pintype "passive"))
    )
    (net (code "91") (name "Net-(U1-VAUX)") (class "Default")
      (node (ref "C0") (pin "1") (pinfunction "1_1") (pintype "passive"))
      (node (ref "U1") (pin "3") (pinfunction "VAUX_3") (pintype "passive"))
    )
    (net (code "92") (name "Net-(U3-ADJ)") (class "Default")
      (node (ref "R5") (pin "2") (pinfunction "2_2") (pintype "passive"))
      (node (ref "R6") (pin "1") (pinfunction "1_1") (pintype "passive"))
      (node (ref "U3") (pin "1") (pinfunction "ADJ_1") (pintype "passive"))
    )
    (net (code "93") (name "Net-(U6-CR)") (class "Default")
      (node (ref "R12") (pin "1") (pinfunction "1_1") (pintype "passive"))
      (node (ref "U6") (pin "9") (pinfunction "CR_9") (pintype "passive"))
    )
    (net (code "94") (name "VCC5V") (class "Default")
      (node (ref "C13") (pin "2") (pinfunction "2_2") (pintype "passive"))
      (node (ref "C14") (pin "1") (pinfunction "1_1") (pintype "passive"))
      (node (ref "C3") (pin "1") (pinfunction "1_1") (pintype "passive"))
      (node (ref "C4") (pin "2") (pinfunction "2_2") (pintype "passive"))
      (node (ref "C5") (pin "2") (pinfunction "2_2") (pintype "passive"))
      (node (ref "C6") (pin "1") (pinfunction "1_1") (pintype "passive"))
      (node (ref "P13") (pin "1") (pinfunction "1_1") (pintype "passive"))
      (node (ref "P13") (pin "2") (pinfunction "2_2") (pintype "passive"))
      (node (ref "P2") (pin "1") (pinfunction "1_1") (pintype "passive"))
      (node (ref "P7") (pin "7") (pinfunction "7_7") (pintype "passive"))
      (node (ref "R2") (pin "2") (pinfunction "2_2") (pintype "passive"))
      (node (ref "R8") (pin "2") (pinfunction "2_2") (pintype "passive"))
      (node (ref "U1") (pin "7") (pinfunction "VOUT_7") (pintype "passive"))
      (node (ref "U1") (pin "8") (pinfunction "VOUT_8") (pintype "passive"))
      (node (ref "U2") (pin "1") (pinfunction "IN_1") (pintype "passive"))
      (node (ref "U4") (pin "1") (pinfunction "IN_1") (pintype "passive"))
      (node (ref "U6") (pin "5") (pinfunction "5V_5") (pintype "passive"))
      (node (ref "U6") (pin "6") (pinfunction "5V_6") (pintype "passive"))
    )
    (net (code "95") (name "VCCBAT") (class "Default")
      (node (ref "D1") (pin "1") (pinfunction "A_1") (pintype "passive"))
      (node (ref "D2") (pin "1") (pinfunction "A_1") (pintype "passive"))
      (node (ref "P10") (pin "1") (pinfunction "VCC_1") (pintype "passive"))
      (node (ref "S6") (pin "1") (pinfunction "1_1") (pintype "passive"))
      (node (ref "S6") (pin "2") (pinfunction "2_2") (pintype "passive"))
    )
    (net (code "96") (name "VCCServo") (class "Default")
      (node (ref "C11") (pin "2") (pinfunction "2_2") (pintype "passive"))
      (node (ref "C12") (pin "1") (pinfunction "1_1") (pintype "passive"))
      (node (ref "P3") (pin "2") (pinfunction "2_2") (pintype "passive"))
      (node (ref "R6") (pin "2") (pinfunction "2_2") (pintype "passive"))
      (node (ref "R9") (pin "2") (pinfunction "2_2") (pintype "passive"))
      (node (ref "U3") (pin "5") (pinfunction "OUT_5") (pintype "passive"))
    )
    (net (code "97") (name "unconnected-(P4-Pad5)") (class "Default")
      (node (ref "P4") (pin "5") (pinfunction "5_5") (pintype "passive+no_connect"))
    )
    (net (code "98") (name "unconnected-(P4-Pad6)") (class "Default")
      (node (ref "P4") (pin "6") (pinfunction "6_6") (pintype "passive+no_connect"))
    )
    (net (code "99") (name "unconnected-(P5-Pad5)") (class "Default")
      (node (ref "P5") (pin "5") (pinfunction "5_5") (pintype "passive+no_connect"))
    )
    (net (code "100") (name "unconnected-(P5-Pad6)") (class "Default")
      (node (ref "P5") (pin "6") (pinfunction "6_6") (pintype "passive+no_connect"))
    )
    (net (code "101") (name "unconnected-(P7-Pad2)") (class "Default")
      (node (ref "P7") (pin "2") (pinfunction "2_2") (pintype "passive+no_connect"))
    )
    (net (code "102") (name "unconnected-(P7-Pad8)") (class "Default")
      (node (ref "P7") (pin "8") (pinfunction "8_8") (pintype "passive+no_connect"))
    )
    (net (code "103") (name "unconnected-(P8-Pad7)") (class "Default")
      (node (ref "P8") (pin "7") (pinfunction "7_7") (pintype "passive+no_connect"))
    )
    (net (code "104") (name "unconnected-(P8-Pad8)") (class "Default")
      (node (ref "P8") (pin "8") (pinfunction "8_8") (pintype "passive+no_connect"))
    )
    (net (code "105") (name "unconnected-(U1-PG-Pad2)") (class "Default")
      (node (ref "U1") (pin "2") (pinfunction "PG_2") (pintype "passive"))
    )
    (net (code "106") (name "unconnected-(U2-NC-Pad4)") (class "Default")
      (node (ref "U2") (pin "4") (pinfunction "NC_4") (pintype "passive+no_connect"))
    )
    (net (code "107") (name "unconnected-(U4-NC-Pad4)") (class "Default")
      (node (ref "U4") (pin "4") (pinfunction "NC_4") (pintype "passive+no_connect"))
    )
    (net (code "108") (name "unconnected-(U6-2DN-Pad22)") (class "Default")
      (node (ref "U6") (pin "22") (pinfunction "2DN_22") (pintype "passive+no_connect"))
    )
    (net (code "109") (name "unconnected-(U6-2DP-Pad21)") (class "Default")
      (node (ref "U6") (pin "21") (pinfunction "2DP_21") (pintype "passive+no_connect"))
    )
    (net (code "110") (name "unconnected-(U6-3V3-Pad3)") (class "Default")
      (node (ref "U6") (pin "3") (pinfunction "3V3_3") (pintype "passive+no_connect"))
    )
    (net (code "111") (name "unconnected-(U6-3V3-Pad4)") (class "Default")
      (node (ref "U6") (pin "4") (pinfunction "3V3_4") (pintype "passive+no_connect"))
    )
    (net (code "112") (name "unconnected-(U6-OF-Pad7)") (class "Default")
      (node (ref "U6") (pin "7") (pinfunction "OF_7") (pintype "passive+no_connect"))
    )
    (net (code "113") (name "unconnected-(U6-WU-Pad8)") (class "Default")
      (node (ref "U6") (pin "8") (pinfunction "WU_8") (pintype "passive+no_connect"))
    )
  )
)
